# Nodino-RC7.net
KiCad netlist of a schematic drawn in EAGLE
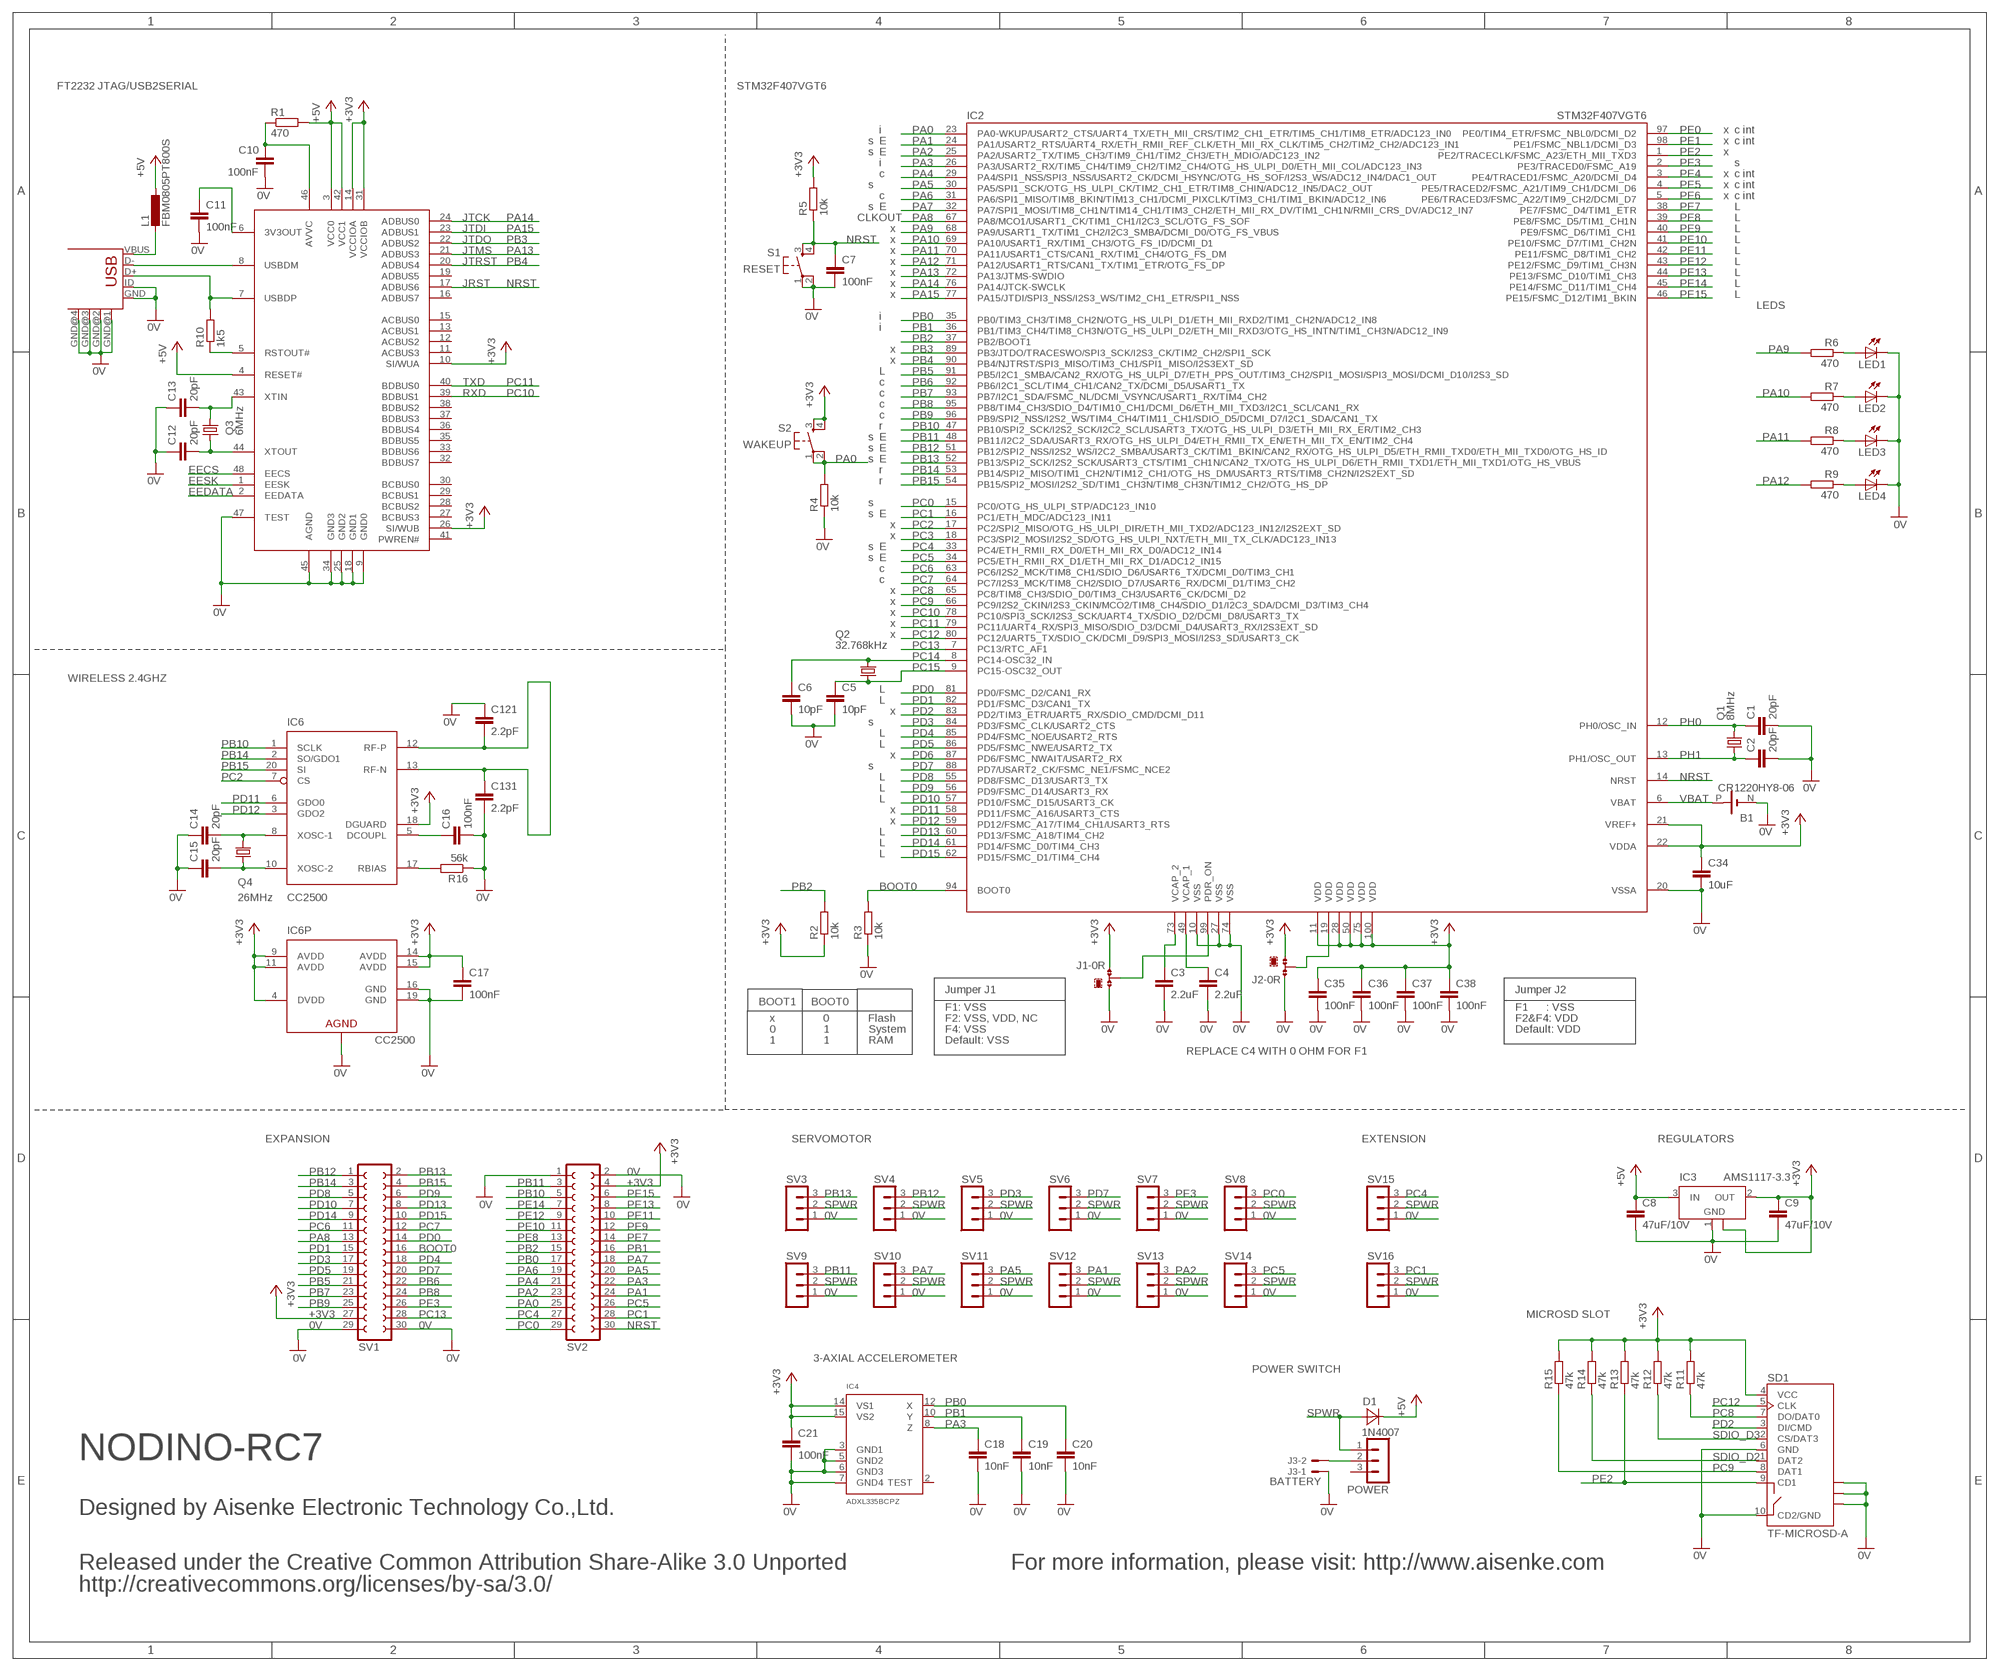
[diagram p0: schematic, sheet 1]

(export (version "E")
  (design (tool "Eeschema 10.0.6"))
  (components
    (comp (ref "B1")
      (value "CR1220HY8-06")
      (footprint "eagle-import:HY8-06")
      (libsource (lib "eagle-import") (part "CR1220HY8-06"))
    )
    (comp (ref "C1")
      (value "20pF")
      (footprint "eagle-import:C0603K")
      (libsource (lib "eagle-import") (part "C-EUC0603K"))
    )
    (comp (ref "C2")
      (value "20pF")
      (footprint "eagle-import:C0603K")
      (libsource (lib "eagle-import") (part "C-EUC0603K"))
    )
    (comp (ref "C3")
      (value "2.2uF")
      (footprint "eagle-import:C0603K")
      (libsource (lib "eagle-import") (part "C-EUC0603K"))
    )
    (comp (ref "C4")
      (value "2.2uF")
      (footprint "eagle-import:C0603K")
      (libsource (lib "eagle-import") (part "C-EUC0603K"))
    )
    (comp (ref "C5")
      (value "10pF")
      (footprint "eagle-import:C0603K")
      (libsource (lib "eagle-import") (part "C-EUC0603K"))
    )
    (comp (ref "C6")
      (value "10pF")
      (footprint "eagle-import:C0603K")
      (libsource (lib "eagle-import") (part "C-EUC0603K"))
    )
    (comp (ref "C7")
      (value "100nF")
      (footprint "eagle-import:C0603K")
      (libsource (lib "eagle-import") (part "C-EUC0603K"))
    )
    (comp (ref "C8")
      (value "47uF/10V")
      (footprint "eagle-import:C3225")
      (libsource (lib "eagle-import") (part "C-EUC3225"))
    )
    (comp (ref "C9")
      (value "47uF/10V")
      (footprint "eagle-import:C3225")
      (libsource (lib "eagle-import") (part "C-EUC3225"))
    )
    (comp (ref "C10")
      (value "100nF")
      (footprint "eagle-import:C0603K")
      (libsource (lib "eagle-import") (part "C-EUC0603K"))
    )
    (comp (ref "C11")
      (value "100nF")
      (footprint "eagle-import:C0603K")
      (libsource (lib "eagle-import") (part "C-EUC0603K"))
    )
    (comp (ref "C12")
      (value "20pF")
      (footprint "eagle-import:C0603K")
      (libsource (lib "eagle-import") (part "C-EUC0603K"))
    )
    (comp (ref "C13")
      (value "20pF")
      (footprint "eagle-import:C0603K")
      (libsource (lib "eagle-import") (part "C-EUC0603K"))
    )
    (comp (ref "C14")
      (value "20pF")
      (footprint "eagle-import:C0603K")
      (libsource (lib "eagle-import") (part "C-EUC0603K"))
    )
    (comp (ref "C15")
      (value "20pF")
      (footprint "eagle-import:C0603K")
      (libsource (lib "eagle-import") (part "C-EUC0603K"))
    )
    (comp (ref "C16")
      (value "100nF")
      (footprint "eagle-import:C0603K")
      (libsource (lib "eagle-import") (part "C-EUC0603K"))
    )
    (comp (ref "C17")
      (value "100nF")
      (footprint "eagle-import:C0603K")
      (libsource (lib "eagle-import") (part "C-EUC0603K"))
    )
    (comp (ref "C18")
      (value "10nF")
      (footprint "eagle-import:C0603K")
      (libsource (lib "eagle-import") (part "C-EUC0603K"))
    )
    (comp (ref "C19")
      (value "10nF")
      (footprint "eagle-import:C0603K")
      (libsource (lib "eagle-import") (part "C-EUC0603K"))
    )
    (comp (ref "C20")
      (value "10nF")
      (footprint "eagle-import:C0603K")
      (libsource (lib "eagle-import") (part "C-EUC0603K"))
    )
    (comp (ref "C21")
      (value "100nF")
      (footprint "eagle-import:C0603K")
      (libsource (lib "eagle-import") (part "C-EUC0603K"))
    )
    (comp (ref "C34")
      (value "10uF")
      (footprint "eagle-import:C0603K")
      (libsource (lib "eagle-import") (part "C-EUC0603K"))
    )
    (comp (ref "C35")
      (value "100nF")
      (footprint "eagle-import:C0603K")
      (libsource (lib "eagle-import") (part "C-EUC0603K"))
    )
    (comp (ref "C36")
      (value "100nF")
      (footprint "eagle-import:C0603K")
      (libsource (lib "eagle-import") (part "C-EUC0603K"))
    )
    (comp (ref "C37")
      (value "100nF")
      (footprint "eagle-import:C0603K")
      (libsource (lib "eagle-import") (part "C-EUC0603K"))
    )
    (comp (ref "C38")
      (value "100nF")
      (footprint "eagle-import:C0603K")
      (libsource (lib "eagle-import") (part "C-EUC0603K"))
    )
    (comp (ref "C121")
      (value "2.2pF")
      (footprint "eagle-import:C0603K")
      (libsource (lib "eagle-import") (part "C-EUC0603K"))
    )
    (comp (ref "C131")
      (value "2.2pF")
      (footprint "eagle-import:C0603K")
      (libsource (lib "eagle-import") (part "C-EUC0603K"))
    )
    (comp (ref "D1")
      (value "1N4007")
      (footprint "eagle-import:DO214AC")
      (libsource (lib "eagle-import") (part "1N4007"))
    )
    (comp (ref "IC1")
      (value "FT2232D")
      (footprint "eagle-import:LQFP48")
      (libsource (lib "eagle-import") (part "FT2232C"))
    )
    (comp (ref "IC2")
      (value "STM32F407VGT6")
      (footprint "eagle-import:LQFP100")
      (libsource (lib "eagle-import") (part "STM32F407VGT6"))
    )
    (comp (ref "IC3")
      (value "AMS1117-3.3")
      (footprint "eagle-import:SOT223")
      (libsource (lib "eagle-import") (part "AMS1117-3.3"))
    )
    (comp (ref "IC4")
      (value "ADXL335BCPZ")
      (footprint "eagle-import:LFCSP16-W")
      (libsource (lib "eagle-import") (part "ADXL335WAVE"))
    )
    (comp (ref "IC6")
      (value "CC2500")
      (footprint "eagle-import:QLP-20")
      (libsource (lib "eagle-import") (part "CC2500"))
    )
    (comp (ref "J1")
      (value "0R-JUMPA0603")
      (footprint "eagle-import:A0R-JMP0603K")
      (libsource (lib "eagle-import") (part "0R-JUMPA0603"))
    )
    (comp (ref "J2")
      (value "0R-JUMPA0603")
      (footprint "eagle-import:A0R-JMP0603K")
      (libsource (lib "eagle-import") (part "0R-JUMPA0603"))
    )
    (comp (ref "J3")
      (value "BATTERY")
      (footprint "eagle-import:6410-02")
      (libsource (lib "eagle-import") (part "22-?-0227-2021"))
    )
    (comp (ref "L1")
      (value "FBM0805PT800S")
      (footprint "eagle-import:L0805")
      (libsource (lib "eagle-import") (part "L-EUL0805"))
    )
    (comp (ref "LED1")
      (value "LEDCHIP-LED0805")
      (footprint "eagle-import:CHIP-LED0805")
      (libsource (lib "eagle-import") (part "LEDCHIP-LED0805"))
    )
    (comp (ref "LED2")
      (value "LEDCHIP-LED0805")
      (footprint "eagle-import:CHIP-LED0805")
      (libsource (lib "eagle-import") (part "LEDCHIP-LED0805"))
    )
    (comp (ref "LED3")
      (value "LEDCHIP-LED0805")
      (footprint "eagle-import:CHIP-LED0805")
      (libsource (lib "eagle-import") (part "LEDCHIP-LED0805"))
    )
    (comp (ref "LED4")
      (value "LEDCHIP-LED0805")
      (footprint "eagle-import:CHIP-LED0805")
      (libsource (lib "eagle-import") (part "LEDCHIP-LED0805"))
    )
    (comp (ref "POWER")
      (value "MA03-1")
      (footprint "eagle-import:MA03-1")
      (fields (field (name "OC_FARNELL") "unknown") (field (name "OC_NEWARK") "unknown"))
      (libsource (lib "eagle-import") (part "MA03-1"))
    )
    (comp (ref "Q1")
      (value "8MHz")
      (footprint "eagle-import:CSM-7X-DU")
      (libsource (lib "eagle-import") (part "CSM-7X-DU"))
    )
    (comp (ref "Q2")
      (value "32.768kHz")
      (footprint "eagle-import:MC-306")
      (fields (field (name "MPN") "MC-306 60.0KHZ  100PPM ,12.5PF"))
      (libsource (lib "eagle-import") (part "MC-306"))
    )
    (comp (ref "Q3")
      (value "6MHz")
      (footprint "eagle-import:CSM-7X-DU")
      (fields (field (name "OC_FARNELL") "unknown") (field (name "OC_NEWARK") "unknown"))
      (libsource (lib "eagle-import") (part "CSM-7X-DU"))
    )
    (comp (ref "Q4")
      (value "26MHz")
      (footprint "eagle-import:CSM-7X-DU")
      (fields (field (name "OC_FARNELL") "unknown") (field (name "OC_NEWARK") "unknown"))
      (libsource (lib "eagle-import") (part "CSM-7X-DU"))
    )
    (comp (ref "R1")
      (value "470")
      (footprint "eagle-import:R0603K")
      (libsource (lib "eagle-import") (part "R-EU_R0603K"))
    )
    (comp (ref "R2")
      (value "10k")
      (footprint "eagle-import:R0603K")
      (libsource (lib "eagle-import") (part "R-EU_R0603K"))
    )
    (comp (ref "R3")
      (value "10k")
      (footprint "eagle-import:R0603K")
      (libsource (lib "eagle-import") (part "R-EU_R0603K"))
    )
    (comp (ref "R4")
      (value "10k")
      (footprint "eagle-import:R0603K")
      (libsource (lib "eagle-import") (part "R-EU_R0603K"))
    )
    (comp (ref "R5")
      (value "10k")
      (footprint "eagle-import:R0603K")
      (libsource (lib "eagle-import") (part "R-EU_R0603K"))
    )
    (comp (ref "R6")
      (value "470")
      (footprint "eagle-import:R0603K")
      (libsource (lib "eagle-import") (part "R-EU_R0603K"))
    )
    (comp (ref "R7")
      (value "470")
      (footprint "eagle-import:R0603K")
      (libsource (lib "eagle-import") (part "R-EU_R0603K"))
    )
    (comp (ref "R8")
      (value "470")
      (footprint "eagle-import:R0603K")
      (libsource (lib "eagle-import") (part "R-EU_R0603K"))
    )
    (comp (ref "R9")
      (value "470")
      (footprint "eagle-import:R0603K")
      (libsource (lib "eagle-import") (part "R-EU_R0603K"))
    )
    (comp (ref "R10")
      (value "1k5")
      (footprint "eagle-import:R0603K")
      (libsource (lib "eagle-import") (part "R-EU_R0603K"))
    )
    (comp (ref "R11")
      (value "47k")
      (footprint "eagle-import:R0603K")
      (libsource (lib "eagle-import") (part "R-EU_R0603K"))
    )
    (comp (ref "R12")
      (value "47k")
      (footprint "eagle-import:R0603K")
      (libsource (lib "eagle-import") (part "R-EU_R0603K"))
    )
    (comp (ref "R13")
      (value "47k")
      (footprint "eagle-import:R0603K")
      (libsource (lib "eagle-import") (part "R-EU_R0603K"))
    )
    (comp (ref "R14")
      (value "47k")
      (footprint "eagle-import:R0603K")
      (libsource (lib "eagle-import") (part "R-EU_R0603K"))
    )
    (comp (ref "R15")
      (value "47k")
      (footprint "eagle-import:R0603K")
      (libsource (lib "eagle-import") (part "R-EU_R0603K"))
    )
    (comp (ref "R16")
      (value "56k")
      (footprint "eagle-import:R0603K")
      (libsource (lib "eagle-import") (part "R-EU_R0603K"))
    )
    (comp (ref "S1")
      (value "RESET")
      (footprint "eagle-import:ALCOSWITCH-SMD")
      (libsource (lib "eagle-import") (part "ALCOSWITCH-SMD"))
    )
    (comp (ref "S2")
      (value "WAKEUP")
      (footprint "eagle-import:ALCOSWITCH-SMD")
      (libsource (lib "eagle-import") (part "ALCOSWITCH-SMD"))
    )
    (comp (ref "SD1")
      (value "TF-MICROSD-A")
      (footprint "eagle-import:MICROSD_CD")
      (libsource (lib "eagle-import") (part "TF-MICROSD-A"))
    )
    (comp (ref "SV1")
      (value "FE15-2")
      (footprint "eagle-import:FE15-2")
      (libsource (lib "eagle-import") (part "FE15-2"))
    )
    (comp (ref "SV2")
      (value "FE15-2")
      (footprint "eagle-import:FE15-2")
      (libsource (lib "eagle-import") (part "FE15-2"))
    )
    (comp (ref "SV3")
      (value "MA03-1")
      (footprint "eagle-import:MA03-1")
      (libsource (lib "eagle-import") (part "MA03-1"))
    )
    (comp (ref "SV4")
      (value "MA03-1")
      (footprint "eagle-import:MA03-1")
      (libsource (lib "eagle-import") (part "MA03-1"))
    )
    (comp (ref "SV5")
      (value "MA03-1")
      (footprint "eagle-import:MA03-1")
      (libsource (lib "eagle-import") (part "MA03-1"))
    )
    (comp (ref "SV6")
      (value "MA03-1")
      (footprint "eagle-import:MA03-1")
      (libsource (lib "eagle-import") (part "MA03-1"))
    )
    (comp (ref "SV7")
      (value "MA03-1")
      (footprint "eagle-import:MA03-1")
      (libsource (lib "eagle-import") (part "MA03-1"))
    )
    (comp (ref "SV8")
      (value "MA03-1")
      (footprint "eagle-import:MA03-1")
      (libsource (lib "eagle-import") (part "MA03-1"))
    )
    (comp (ref "SV9")
      (value "MA03-1")
      (footprint "eagle-import:MA03-1")
      (libsource (lib "eagle-import") (part "MA03-1"))
    )
    (comp (ref "SV10")
      (value "MA03-1")
      (footprint "eagle-import:MA03-1")
      (libsource (lib "eagle-import") (part "MA03-1"))
    )
    (comp (ref "SV11")
      (value "MA03-1")
      (footprint "eagle-import:MA03-1")
      (libsource (lib "eagle-import") (part "MA03-1"))
    )
    (comp (ref "SV12")
      (value "MA03-1")
      (footprint "eagle-import:MA03-1")
      (libsource (lib "eagle-import") (part "MA03-1"))
    )
    (comp (ref "SV13")
      (value "MA03-1")
      (footprint "eagle-import:MA03-1")
      (libsource (lib "eagle-import") (part "MA03-1"))
    )
    (comp (ref "SV14")
      (value "MA03-1")
      (footprint "eagle-import:MA03-1")
      (libsource (lib "eagle-import") (part "MA03-1"))
    )
    (comp (ref "SV15")
      (value "MA03-1")
      (footprint "eagle-import:MA03-1")
      (libsource (lib "eagle-import") (part "MA03-1"))
    )
    (comp (ref "SV16")
      (value "MA03-1")
      (footprint "eagle-import:MA03-1")
      (libsource (lib "eagle-import") (part "MA03-1"))
    )
    (comp (ref "USB1")
      (value "USB-SHIELD")
      (footprint "eagle-import:USB-M-S1")
      (libsource (lib "eagle-import") (part "USB-SHIELD"))
    )
  )
  (nets
    (net (code "1") (name "+3V3") (class "Default")
      (node (ref "C17") (pin "1") (pinfunction "1_1") (pintype "passive"))
      (node (ref "C21") (pin "1") (pinfunction "1_1") (pintype "passive"))
      (node (ref "C34") (pin "1") (pinfunction "1_1") (pintype "passive"))
      (node (ref "C35") (pin "1") (pinfunction "1_1") (pintype "passive"))
      (node (ref "C36") (pin "1") (pinfunction "1_1") (pintype "passive"))
      (node (ref "C37") (pin "1") (pinfunction "1_1") (pintype "passive"))
      (node (ref "C38") (pin "1") (pinfunction "1_1") (pintype "passive"))
      (node (ref "C9") (pin "1") (pinfunction "1_1") (pintype "passive"))
      (node (ref "IC1") (pin "10") (pinfunction "SI/WUA_10") (pintype "bidirectional"))
      (node (ref "IC1") (pin "14") (pinfunction "VCCIOA_14") (pintype "bidirectional"))
      (node (ref "IC1") (pin "26") (pinfunction "SI/WUB_26") (pintype "bidirectional"))
      (node (ref "IC1") (pin "31") (pinfunction "VCCIOB_31") (pintype "bidirectional"))
      (node (ref "IC2") (pin "100") (pinfunction "VDD_100") (pintype "power_in"))
      (node (ref "IC2") (pin "11") (pinfunction "VDD_11") (pintype "power_in"))
      (node (ref "IC2") (pin "21") (pinfunction "VREF+_21") (pintype "input"))
      (node (ref "IC2") (pin "22") (pinfunction "VDDA_22") (pintype "power_in"))
      (node (ref "IC2") (pin "28") (pinfunction "VDD_28") (pintype "power_in"))
      (node (ref "IC2") (pin "50") (pinfunction "VDD_50") (pintype "power_in"))
      (node (ref "IC2") (pin "75") (pinfunction "VDD_75") (pintype "power_in"))
      (node (ref "IC3") (pin "2") (pinfunction "OUT_2") (pintype "output"))
      (node (ref "IC3") (pin "4") (pinfunction "GND_4") (pintype "power_in"))
      (node (ref "IC4") (pin "14") (pinfunction "VS1_14") (pintype "bidirectional"))
      (node (ref "IC4") (pin "15") (pinfunction "VS2_15") (pintype "bidirectional"))
      (node (ref "IC6") (pin "11") (pinfunction "AVDD_11") (pintype "power_in"))
      (node (ref "IC6") (pin "14") (pinfunction "AVDD_14") (pintype "power_in"))
      (node (ref "IC6") (pin "15") (pinfunction "AVDD_15") (pintype "power_in"))
      (node (ref "IC6") (pin "18") (pinfunction "DGUARD_18") (pintype "power_in"))
      (node (ref "IC6") (pin "4") (pinfunction "DVDD_4") (pintype "power_in"))
      (node (ref "IC6") (pin "9") (pinfunction "AVDD_9") (pintype "power_in"))
      (node (ref "J1") (pin "3") (pinfunction "3_3") (pintype "passive"))
      (node (ref "J2") (pin "1") (pinfunction "1_1") (pintype "passive"))
      (node (ref "R11") (pin "2") (pinfunction "2_2") (pintype "passive"))
      (node (ref "R12") (pin "2") (pinfunction "2_2") (pintype "passive"))
      (node (ref "R13") (pin "2") (pinfunction "2_2") (pintype "passive"))
      (node (ref "R14") (pin "2") (pinfunction "2_2") (pintype "passive"))
      (node (ref "R15") (pin "2") (pinfunction "2_2") (pintype "passive"))
      (node (ref "R2") (pin "1") (pinfunction "1_1") (pintype "passive"))
      (node (ref "R5") (pin "2") (pinfunction "2_2") (pintype "passive"))
      (node (ref "S2") (pin "3") (pinfunction "S_3") (pintype "passive"))
      (node (ref "S2") (pin "4") (pinfunction "S1_4") (pintype "passive"))
      (node (ref "SD1") (pin "4") (pinfunction "VCC_4") (pintype "power_in"))
      (node (ref "SV1") (pin "27") (pinfunction "27_27") (pintype "passive"))
      (node (ref "SV2") (pin "4") (pinfunction "4_4") (pintype "passive"))
    )
    (net (code "2") (name "+5V") (class "Default")
      (node (ref "C8") (pin "1") (pinfunction "1_1") (pintype "passive"))
      (node (ref "D1") (pin "C") (pinfunction "C_C") (pintype "passive"))
      (node (ref "IC1") (pin "3") (pinfunction "VCC0_3") (pintype "bidirectional"))
      (node (ref "IC1") (pin "4") (pinfunction "RESET#_4") (pintype "bidirectional"))
      (node (ref "IC1") (pin "42") (pinfunction "VCC1_42") (pintype "bidirectional"))
      (node (ref "IC3") (pin "3") (pinfunction "IN_3") (pintype "input"))
      (node (ref "L1") (pin "1") (pinfunction "1_1") (pintype "passive"))
      (node (ref "R1") (pin "2") (pinfunction "2_2") (pintype "passive"))
    )
    (net (code "3") (name "/BOOT0") (class "Default")
      (node (ref "IC2") (pin "94") (pinfunction "BOOT0_94") (pintype "input"))
      (node (ref "R3") (pin "2") (pinfunction "2_2") (pintype "passive"))
      (node (ref "SV1") (pin "16") (pinfunction "16_16") (pintype "passive"))
    )
    (net (code "4") (name "/EECS") (class "Default")
      (node (ref "IC1") (pin "48") (pinfunction "EECS_48") (pintype "bidirectional"))
    )
    (net (code "5") (name "/EEDATA") (class "Default")
      (node (ref "IC1") (pin "2") (pinfunction "EEDATA_2") (pintype "bidirectional"))
    )
    (net (code "6") (name "/EESK") (class "Default")
      (node (ref "IC1") (pin "1") (pinfunction "EESK_1") (pintype "bidirectional"))
    )
    (net (code "7") (name "/NRST") (class "Default")
      (node (ref "C7") (pin "1") (pinfunction "1_1") (pintype "passive"))
      (node (ref "IC1") (pin "17") (pinfunction "ADBUS6_17") (pintype "bidirectional"))
      (node (ref "IC2") (pin "14") (pinfunction "NRST_14") (pintype "input"))
      (node (ref "R5") (pin "1") (pinfunction "1_1") (pintype "passive"))
      (node (ref "S1") (pin "3") (pinfunction "S_3") (pintype "passive"))
      (node (ref "S1") (pin "4") (pinfunction "S1_4") (pintype "passive"))
      (node (ref "SV2") (pin "30") (pinfunction "30_30") (pintype "passive"))
    )
    (net (code "8") (name "/PA0") (class "Default")
      (node (ref "IC2") (pin "23") (pinfunction "PA0-WKUP/USART2_CTS/UART4_TX/ETH_MII_CRS/TIM2_CH1_ETR/TIM5_CH1/TIM8_ETR/ADC123_IN0_23") (pintype "bidirectional"))
      (node (ref "R4") (pin "2") (pinfunction "2_2") (pintype "passive"))
      (node (ref "S2") (pin "1") (pinfunction "P_1") (pintype "passive"))
      (node (ref "S2") (pin "2") (pinfunction "P1_2") (pintype "passive"))
      (node (ref "SV2") (pin "25") (pinfunction "25_25") (pintype "passive"))
    )
    (net (code "9") (name "/PA1") (class "Default")
      (node (ref "IC2") (pin "24") (pinfunction "PA1/USART2_RTS/UART4_RX/ETH_RMII_REF_CLK/ETH_MII_RX_CLK/TIM5_CH2/TIM2_CH2/ADC123_IN1_24") (pintype "bidirectional"))
      (node (ref "SV12") (pin "3") (pinfunction "3_3") (pintype "passive"))
      (node (ref "SV2") (pin "24") (pinfunction "24_24") (pintype "passive"))
    )
    (net (code "10") (name "/PA2") (class "Default")
      (node (ref "IC2") (pin "25") (pinfunction "PA2/USART2_TX/TIM5_CH3/TIM9_CH1/TIM2_CH3/ETH_MDIO/ADC123_IN2_25") (pintype "bidirectional"))
      (node (ref "SV13") (pin "3") (pinfunction "3_3") (pintype "passive"))
      (node (ref "SV2") (pin "23") (pinfunction "23_23") (pintype "passive"))
    )
    (net (code "11") (name "/PA3") (class "Default")
      (node (ref "C18") (pin "1") (pinfunction "1_1") (pintype "passive"))
      (node (ref "IC2") (pin "26") (pinfunction "PA3/USART2_RX/TIM5_CH4/TIM9_CH2/TIM2_CH4/OTG_HS_ULPI_D0/ETH_MII_COL/ADC123_IN3_26") (pintype "bidirectional"))
      (node (ref "IC4") (pin "8") (pinfunction "Z_8") (pintype "bidirectional"))
      (node (ref "SV2") (pin "22") (pinfunction "22_22") (pintype "passive"))
    )
    (net (code "12") (name "/PA4") (class "Default")
      (node (ref "IC2") (pin "29") (pinfunction "PA4/SPI1_NSS/SPI3_NSS/USART2_CK/DCMI_HSYNC/OTG_HS_SOF/I2S3_WS/ADC12_IN4/DAC1_OUT_29") (pintype "bidirectional"))
      (node (ref "SV2") (pin "21") (pinfunction "21_21") (pintype "passive"))
    )
    (net (code "13") (name "/PA5") (class "Default")
      (node (ref "IC2") (pin "30") (pinfunction "PA5/SPI1_SCK/OTG_HS_ULPI_CK/TIM2_CH1_ETR/TIM8_CHIN/ADC12_IN5/DAC2_OUT_30") (pintype "bidirectional"))
      (node (ref "SV11") (pin "3") (pinfunction "3_3") (pintype "passive"))
      (node (ref "SV2") (pin "20") (pinfunction "20_20") (pintype "passive"))
    )
    (net (code "14") (name "/PA6") (class "Default")
      (node (ref "IC2") (pin "31") (pinfunction "PA6/SPI1_MISO/TIM8_BKIN/TIM13_CH1/DCMI_PIXCLK/TIM3_CH1/TIM1_BKIN/ADC12_IN6_31") (pintype "bidirectional"))
      (node (ref "SV2") (pin "19") (pinfunction "19_19") (pintype "passive"))
    )
    (net (code "15") (name "/PA7") (class "Default")
      (node (ref "IC2") (pin "32") (pinfunction "PA7/SPI1_MOSI/TIM8_CH1N/TIM14_CH1/TIM3_CH2/ETH_MII_RX_DV/TIM1_CH1N/RMII_CRS_DV/ADC12_IN7_32") (pintype "bidirectional"))
      (node (ref "SV10") (pin "3") (pinfunction "3_3") (pintype "passive"))
      (node (ref "SV2") (pin "18") (pinfunction "18_18") (pintype "passive"))
    )
    (net (code "16") (name "/PA8") (class "Default")
      (node (ref "IC2") (pin "67") (pinfunction "PA8/MCO1/USART1_CK/TIM1_CH1/I2C3_SCL/OTG_FS_SOF_67") (pintype "bidirectional"))
      (node (ref "SV1") (pin "13") (pinfunction "13_13") (pintype "passive"))
    )
    (net (code "17") (name "/PA9") (class "Default")
      (node (ref "IC2") (pin "68") (pinfunction "PA9/USART1_TX/TIM1_CH2/I2C3_SMBA/DCMI_D0/OTG_FS_VBUS_68") (pintype "bidirectional"))
      (node (ref "R6") (pin "2") (pinfunction "2_2") (pintype "passive"))
    )
    (net (code "18") (name "/PA10") (class "Default")
      (node (ref "IC2") (pin "69") (pinfunction "PA10/USART1_RX/TIM1_CH3/OTG_FS_ID/DCMI_D1_69") (pintype "bidirectional"))
      (node (ref "R7") (pin "2") (pinfunction "2_2") (pintype "passive"))
    )
    (net (code "19") (name "/PA11") (class "Default")
      (node (ref "IC2") (pin "70") (pinfunction "PA11/USART1_CTS/CAN1_RX/TIM1_CH4/OTG_FS_DM_70") (pintype "bidirectional"))
      (node (ref "R8") (pin "2") (pinfunction "2_2") (pintype "passive"))
    )
    (net (code "20") (name "/PA12") (class "Default")
      (node (ref "IC2") (pin "71") (pinfunction "PA12/USART1_RTS/CAN1_TX/TIM1_ETR/OTG_FS_DP_71") (pintype "bidirectional"))
      (node (ref "R9") (pin "2") (pinfunction "2_2") (pintype "passive"))
    )
    (net (code "21") (name "/PA13") (class "Default")
      (node (ref "IC1") (pin "21") (pinfunction "ADBUS3_21") (pintype "bidirectional"))
      (node (ref "IC2") (pin "72") (pinfunction "PA13/JTMS-SWDIO_72") (pintype "bidirectional"))
    )
    (net (code "22") (name "/PA14") (class "Default")
      (node (ref "IC1") (pin "24") (pinfunction "ADBUS0_24") (pintype "bidirectional"))
      (node (ref "IC2") (pin "76") (pinfunction "PA14/JTCK-SWCLK_76") (pintype "bidirectional"))
    )
    (net (code "23") (name "/PA15") (class "Default")
      (node (ref "IC1") (pin "23") (pinfunction "ADBUS1_23") (pintype "bidirectional"))
      (node (ref "IC2") (pin "77") (pinfunction "PA15/JTDI/SPI3_NSS/I2S3_WS/TIM2_CH1_ETR/SPI1_NSS_77") (pintype "bidirectional"))
    )
    (net (code "24") (name "/PB0") (class "Default")
      (node (ref "C20") (pin "1") (pinfunction "1_1") (pintype "passive"))
      (node (ref "IC2") (pin "35") (pinfunction "PB0/TIM3_CH3/TIM8_CH2N/OTG_HS_ULPI_D1/ETH_MII_RXD2/TIM1_CH2N/ADC12_IN8_35") (pintype "bidirectional"))
      (node (ref "IC4") (pin "12") (pinfunction "X_12") (pintype "bidirectional"))
      (node (ref "SV2") (pin "17") (pinfunction "17_17") (pintype "passive"))
    )
    (net (code "25") (name "/PB1") (class "Default")
      (node (ref "C19") (pin "1") (pinfunction "1_1") (pintype "passive"))
      (node (ref "IC2") (pin "36") (pinfunction "PB1/TIM3_CH4/TIM8_CH3N/OTG_HS_ULPI_D2/ETH_MII_RXD3/OTG_HS_INTN/TIM1_CH3N/ADC12_IN9_36") (pintype "bidirectional"))
      (node (ref "IC4") (pin "10") (pinfunction "Y_10") (pintype "bidirectional"))
      (node (ref "SV2") (pin "16") (pinfunction "16_16") (pintype "passive"))
    )
    (net (code "26") (name "/PB2") (class "Default")
      (node (ref "IC2") (pin "37") (pinfunction "PB2/BOOT1_37") (pintype "bidirectional"))
      (node (ref "R2") (pin "2") (pinfunction "2_2") (pintype "passive"))
      (node (ref "SV2") (pin "15") (pinfunction "15_15") (pintype "passive"))
    )
    (net (code "27") (name "/PB3") (class "Default")
      (node (ref "IC1") (pin "22") (pinfunction "ADBUS2_22") (pintype "bidirectional"))
      (node (ref "IC2") (pin "89") (pinfunction "PB3/JTDO/TRACESWO/SPI3_SCK/I2S3_CK/TIM2_CH2/SPI1_SCK_89") (pintype "bidirectional"))
    )
    (net (code "28") (name "/PB4") (class "Default")
      (node (ref "IC1") (pin "20") (pinfunction "ADBUS4_20") (pintype "bidirectional"))
      (node (ref "IC2") (pin "90") (pinfunction "PB4/NJTRST/SPI3_MISO/TIM3_CH1/SPI1_MISO/I2S3EXT_SD_90") (pintype "bidirectional"))
    )
    (net (code "29") (name "/PB5") (class "Default")
      (node (ref "IC2") (pin "91") (pinfunction "PB5/I2C1_SMBA/CAN2_RX/OTG_HS_ULPI_D7/ETH_PPS_OUT/TIM3_CH2/SPI1_MOSI/SPI3_MOSI/DCMI_D10/I2S3_SD_91") (pintype "bidirectional"))
      (node (ref "SV1") (pin "21") (pinfunction "21_21") (pintype "passive"))
    )
    (net (code "30") (name "/PB6") (class "Default")
      (node (ref "IC2") (pin "92") (pinfunction "PB6/I2C1_SCL/TIM4_CH1/CAN2_TX/DCMI_D5/USART1_TX_92") (pintype "bidirectional"))
      (node (ref "SV1") (pin "22") (pinfunction "22_22") (pintype "passive"))
    )
    (net (code "31") (name "/PB7") (class "Default")
      (node (ref "IC2") (pin "93") (pinfunction "PB7/I2C1_SDA/FSMC_NL/DCMI_VSYNC/USART1_RX/TIM4_CH2_93") (pintype "bidirectional"))
      (node (ref "SV1") (pin "23") (pinfunction "23_23") (pintype "passive"))
    )
    (net (code "32") (name "/PB8") (class "Default")
      (node (ref "IC2") (pin "95") (pinfunction "PB8/TIM4_CH3/SDIO_D4/TIM10_CH1/DCMI_D6/ETH_MII_TXD3/I2C1_SCL/CAN1_RX_95") (pintype "bidirectional"))
      (node (ref "SV1") (pin "24") (pinfunction "24_24") (pintype "passive"))
    )
    (net (code "33") (name "/PB9") (class "Default")
      (node (ref "IC2") (pin "96") (pinfunction "PB9/SPI2_NSS/I2S2_WS/TIM4_CH4/TIM11_CH1/SDIO_D5/DCMI_D7/I2C1_SDA/CAN1_TX_96") (pintype "bidirectional"))
      (node (ref "SV1") (pin "25") (pinfunction "25_25") (pintype "passive"))
    )
    (net (code "34") (name "/PB10") (class "Default")
      (node (ref "IC2") (pin "47") (pinfunction "PB10/SPI2_SCK/I2S2_SCK/I2C2_SCL/USART3_TX/OTG_HS_ULPI_D3/ETH_MII_RX_ER/TIM2_CH3_47") (pintype "bidirectional"))
      (node (ref "IC6") (pin "1") (pinfunction "SCLK_1") (pintype "input"))
      (node (ref "SV2") (pin "5") (pinfunction "5_5") (pintype "passive"))
    )
    (net (code "35") (name "/PB11") (class "Default")
      (node (ref "IC2") (pin "48") (pinfunction "PB11/I2C2_SDA/USART3_RX/OTG_HS_ULPI_D4/ETH_RMII_TX_EN/ETH_MII_TX_EN/TIM2_CH4_48") (pintype "bidirectional"))
      (node (ref "SV2") (pin "3") (pinfunction "3_3") (pintype "passive"))
      (node (ref "SV9") (pin "3") (pinfunction "3_3") (pintype "passive"))
    )
    (net (code "36") (name "/PB12") (class "Default")
      (node (ref "IC2") (pin "51") (pinfunction "PB12/SPI2_NSS/I2S2_WS/I2C2_SMBA/USART3_CK/TIM1_BKIN/CAN2_RX/OTG_HS_ULPI_D5/ETH_RMII_TXD0/ETH_MII_TXD0/OTG_HS_ID_51") (pintype "bidirectional"))
      (node (ref "SV1") (pin "1") (pinfunction "1_1") (pintype "passive"))
      (node (ref "SV4") (pin "3") (pinfunction "3_3") (pintype "passive"))
    )
    (net (code "37") (name "/PB13") (class "Default")
      (node (ref "IC2") (pin "52") (pinfunction "PB13/SPI2_SCK/I2S2_SCK/USART3_CTS/TIM1_CH1N/CAN2_TX/OTG_HS_ULPI_D6/ETH_RMII_TXD1/ETH_MII_TXD1/OTG_HS_VBUS_52") (pintype "bidirectional"))
      (node (ref "SV1") (pin "2") (pinfunction "2_2") (pintype "passive"))
      (node (ref "SV3") (pin "3") (pinfunction "3_3") (pintype "passive"))
    )
    (net (code "38") (name "/PB14") (class "Default")
      (node (ref "IC2") (pin "53") (pinfunction "PB14/SPI2_MISO/TIM1_CH2N/TIM12_CH1/OTG_HS_DM/USART3_RTS/TIM8_CH2N/I2S2EXT_SD_53") (pintype "bidirectional"))
      (node (ref "IC6") (pin "2") (pinfunction "SO/GDO1_2") (pintype "output"))
      (node (ref "SV1") (pin "3") (pinfunction "3_3") (pintype "passive"))
    )
    (net (code "39") (name "/PB15") (class "Default")
      (node (ref "IC2") (pin "54") (pinfunction "PB15/SPI2_MOSI/I2S2_SD/TIM1_CH3N/TIM8_CH3N/TIM12_CH2/OTG_HS_DP_54") (pintype "bidirectional"))
      (node (ref "IC6") (pin "20") (pinfunction "SI_20") (pintype "input"))
      (node (ref "SV1") (pin "4") (pinfunction "4_4") (pintype "passive"))
    )
    (net (code "40") (name "/PC0") (class "Default")
      (node (ref "IC2") (pin "15") (pinfunction "PC0/OTG_HS_ULPI_STP/ADC123_IN10_15") (pintype "bidirectional"))
      (node (ref "SV2") (pin "29") (pinfunction "29_29") (pintype "passive"))
      (node (ref "SV8") (pin "3") (pinfunction "3_3") (pintype "passive"))
    )
    (net (code "41") (name "/PC1") (class "Default")
      (node (ref "IC2") (pin "16") (pinfunction "PC1/ETH_MDC/ADC123_IN11_16") (pintype "bidirectional"))
      (node (ref "SV16") (pin "3") (pinfunction "3_3") (pintype "passive"))
      (node (ref "SV2") (pin "28") (pinfunction "28_28") (pintype "passive"))
    )
    (net (code "42") (name "/PC2") (class "Default")
      (node (ref "IC2") (pin "17") (pinfunction "PC2/SPI2_MISO/OTG_HS_ULPI_DIR/ETH_MII_TXD2/ADC123_IN12/I2S2EXT_SD_17") (pintype "bidirectional"))
      (node (ref "IC6") (pin "7") (pinfunction "CS_7") (pintype "input"))
    )
    (net (code "43") (name "/PC3") (class "Default")
      (node (ref "IC2") (pin "18") (pinfunction "PC3/SPI2_MOSI/I2S2_SD/OTG_HS_ULPI_NXT/ETH_MII_TX_CLK/ADC123_IN13_18") (pintype "bidirectional"))
    )
    (net (code "44") (name "/PC4") (class "Default")
      (node (ref "IC2") (pin "33") (pinfunction "PC4/ETH_RMII_RX_D0/ETH_MII_RX_D0/ADC12_IN14_33") (pintype "bidirectional"))
      (node (ref "SV15") (pin "3") (pinfunction "3_3") (pintype "passive"))
      (node (ref "SV2") (pin "27") (pinfunction "27_27") (pintype "passive"))
    )
    (net (code "45") (name "/PC5") (class "Default")
      (node (ref "IC2") (pin "34") (pinfunction "PC5/ETH_RMII_RX_D1/ETH_MII_RX_D1/ADC12_IN15_34") (pintype "bidirectional"))
      (node (ref "SV14") (pin "3") (pinfunction "3_3") (pintype "passive"))
      (node (ref "SV2") (pin "26") (pinfunction "26_26") (pintype "passive"))
    )
    (net (code "46") (name "/PC6") (class "Default")
      (node (ref "IC2") (pin "63") (pinfunction "PC6/I2S2_MCK/TIM8_CH1/SDIO_D6/USART6_TX/DCMI_D0/TIM3_CH1_63") (pintype "bidirectional"))
      (node (ref "SV1") (pin "11") (pinfunction "11_11") (pintype "passive"))
    )
    (net (code "47") (name "/PC7") (class "Default")
      (node (ref "IC2") (pin "64") (pinfunction "PC7/I2S3_MCK/TIM8_CH2/SDIO_D7/USART6_RX/DCMI_D1/TIM3_CH2_64") (pintype "bidirectional"))
      (node (ref "SV1") (pin "12") (pinfunction "12_12") (pintype "passive"))
    )
    (net (code "48") (name "/PC8") (class "Default")
      (node (ref "IC2") (pin "65") (pinfunction "PC8/TIM8_CH3/SDIO_D0/TIM3_CH3/USART6_CK/DCMI_D2_65") (pintype "bidirectional"))
      (node (ref "R11") (pin "1") (pinfunction "1_1") (pintype "passive"))
      (node (ref "SD1") (pin "7") (pinfunction "DO/DAT0_7") (pintype "bidirectional"))
    )
    (net (code "49") (name "/PC9") (class "Default")
      (node (ref "IC2") (pin "66") (pinfunction "PC9/I2S2_CKIN/I2S3_CKIN/MCO2/TIM8_CH4/SDIO_D1/I2C3_SDA/DCMI_D3/TIM3_CH4_66") (pintype "bidirectional"))
      (node (ref "R15") (pin "1") (pinfunction "1_1") (pintype "passive"))
      (node (ref "SD1") (pin "8") (pinfunction "DAT1_8") (pintype "bidirectional"))
    )
    (net (code "50") (name "/PC10") (class "Default")
      (node (ref "IC1") (pin "39") (pinfunction "BDBUS1_39") (pintype "bidirectional"))
      (node (ref "IC2") (pin "78") (pinfunction "PC10/SPI3_SCK/I2S3_SCK/UART4_TX/SDIO_D2/DCMI_D8/USART3_TX_78") (pintype "bidirectional"))
    )
    (net (code "51") (name "/PC11") (class "Default")
      (node (ref "IC1") (pin "40") (pinfunction "BDBUS0_40") (pintype "bidirectional"))
      (node (ref "IC2") (pin "79") (pinfunction "PC11/UART4_RX/SPI3_MISO/SDIO_D3/DCMI_D4/USART3_RX/I2S3EXT_SD_79") (pintype "bidirectional"))
    )
    (net (code "52") (name "/PC12") (class "Default")
      (node (ref "IC2") (pin "80") (pinfunction "PC12/UART5_TX/SDIO_CK/DCMI_D9/SPI3_MOSI/I2S3_SD/USART3_CK_80") (pintype "bidirectional"))
      (node (ref "SD1") (pin "5") (pinfunction "CLK_5") (pintype "input"))
    )
    (net (code "53") (name "/PC13") (class "Default")
      (node (ref "IC2") (pin "7") (pinfunction "PC13/RTC_AF1_7") (pintype "bidirectional"))
      (node (ref "SV1") (pin "28") (pinfunction "28_28") (pintype "passive"))
    )
    (net (code "54") (name "/PC14") (class "Default")
      (node (ref "C6") (pin "1") (pinfunction "1_1") (pintype "passive"))
      (node (ref "IC2") (pin "8") (pinfunction "PC14-OSC32_IN_8") (pintype "bidirectional"))
      (node (ref "Q2") (pin "4") (pinfunction "2_4") (pintype "passive"))
    )
    (net (code "55") (name "/PC15") (class "Default")
      (node (ref "C5") (pin "1") (pinfunction "1_1") (pintype "passive"))
      (node (ref "IC2") (pin "9") (pinfunction "PC15-OSC32_OUT_9") (pintype "bidirectional"))
      (node (ref "Q2") (pin "1") (pinfunction "1_1") (pintype "passive"))
    )
    (net (code "56") (name "/PD0") (class "Default")
      (node (ref "IC2") (pin "81") (pinfunction "PD0/FSMC_D2/CAN1_RX_81") (pintype "bidirectional"))
      (node (ref "SV1") (pin "14") (pinfunction "14_14") (pintype "passive"))
    )
    (net (code "57") (name "/PD1") (class "Default")
      (node (ref "IC2") (pin "82") (pinfunction "PD1/FSMC_D3/CAN1_TX_82") (pintype "bidirectional"))
      (node (ref "SV1") (pin "15") (pinfunction "15_15") (pintype "passive"))
    )
    (net (code "58") (name "/PD2") (class "Default")
      (node (ref "IC2") (pin "83") (pinfunction "PD2/TIM3_ETR/UART5_RX/SDIO_CMD/DCMI_D11_83") (pintype "bidirectional"))
      (node (ref "SD1") (pin "3") (pinfunction "DI/CMD_3") (pintype "bidirectional"))
    )
    (net (code "59") (name "/PD3") (class "Default")
      (node (ref "IC2") (pin "84") (pinfunction "PD3/FSMC_CLK/USART2_CTS_84") (pintype "bidirectional"))
      (node (ref "SV1") (pin "17") (pinfunction "17_17") (pintype "passive"))
      (node (ref "SV5") (pin "3") (pinfunction "3_3") (pintype "passive"))
    )
    (net (code "60") (name "/PD4") (class "Default")
      (node (ref "IC2") (pin "85") (pinfunction "PD4/FSMC_NOE/USART2_RTS_85") (pintype "bidirectional"))
      (node (ref "SV1") (pin "18") (pinfunction "18_18") (pintype "passive"))
    )
    (net (code "61") (name "/PD5") (class "Default")
      (node (ref "IC2") (pin "86") (pinfunction "PD5/FSMC_NWE/USART2_TX_86") (pintype "bidirectional"))
      (node (ref "SV1") (pin "19") (pinfunction "19_19") (pintype "passive"))
    )
    (net (code "62") (name "/PD6") (class "Default")
      (node (ref "IC2") (pin "87") (pinfunction "PD6/FSMC_NWAIT/USART2_RX_87") (pintype "bidirectional"))
    )
    (net (code "63") (name "/PD7") (class "Default")
      (node (ref "IC2") (pin "88") (pinfunction "PD7/USART2_CK/FSMC_NE1/FSMC_NCE2_88") (pintype "bidirectional"))
      (node (ref "SV1") (pin "20") (pinfunction "20_20") (pintype "passive"))
      (node (ref "SV6") (pin "3") (pinfunction "3_3") (pintype "passive"))
    )
    (net (code "64") (name "/PD8") (class "Default")
      (node (ref "IC2") (pin "55") (pinfunction "PD8/FSMC_D13/USART3_TX_55") (pintype "bidirectional"))
      (node (ref "SV1") (pin "5") (pinfunction "5_5") (pintype "passive"))
    )
    (net (code "65") (name "/PD9") (class "Default")
      (node (ref "IC2") (pin "56") (pinfunction "PD9/FSMC_D14/USART3_RX_56") (pintype "bidirectional"))
      (node (ref "SV1") (pin "6") (pinfunction "6_6") (pintype "passive"))
    )
    (net (code "66") (name "/PD10") (class "Default")
      (node (ref "IC2") (pin "57") (pinfunction "PD10/FSMC_D15/USART3_CK_57") (pintype "bidirectional"))
      (node (ref "SV1") (pin "7") (pinfunction "7_7") (pintype "passive"))
    )
    (net (code "67") (name "/PD11") (class "Default")
      (node (ref "IC2") (pin "58") (pinfunction "PD11/FSMC_A16/USART3_CTS_58") (pintype "bidirectional"))
      (node (ref "IC6") (pin "6") (pinfunction "GDO0_6") (pintype "output"))
    )
    (net (code "68") (name "/PD12") (class "Default")
      (node (ref "IC2") (pin "59") (pinfunction "PD12/FSMC_A17/TIM4_CH1/USART3_RTS_59") (pintype "bidirectional"))
      (node (ref "IC6") (pin "3") (pinfunction "GDO2_3") (pintype "output"))
    )
    (net (code "69") (name "/PD13") (class "Default")
      (node (ref "IC2") (pin "60") (pinfunction "PD13/FSMC_A18/TIM4_CH2_60") (pintype "bidirectional"))
      (node (ref "SV1") (pin "8") (pinfunction "8_8") (pintype "passive"))
    )
    (net (code "70") (name "/PD14") (class "Default")
      (node (ref "IC2") (pin "61") (pinfunction "PD14/FSMC_D0/TIM4_CH3_61") (pintype "bidirectional"))
      (node (ref "SV1") (pin "9") (pinfunction "9_9") (pintype "passive"))
    )
    (net (code "71") (name "/PD15") (class "Default")
      (node (ref "IC2") (pin "62") (pinfunction "PD15/FSMC_D1/TIM4_CH4_62") (pintype "bidirectional"))
      (node (ref "SV1") (pin "10") (pinfunction "10_10") (pintype "passive"))
    )
    (net (code "72") (name "/PE0") (class "Default")
      (node (ref "IC2") (pin "97") (pinfunction "PE0/TIM4_ETR/FSMC_NBL0/DCMI_D2_97") (pintype "bidirectional"))
    )
    (net (code "73") (name "/PE1") (class "Default")
      (node (ref "IC2") (pin "98") (pinfunction "PE1/FSMC_NBL1/DCMI_D3_98") (pintype "bidirectional"))
    )
    (net (code "74") (name "/PE2") (class "Default")
      (node (ref "IC2") (pin "1") (pinfunction "PE2/TRACECLK/FSMC_A23/ETH_MII_TXD3_1") (pintype "bidirectional"))
      (node (ref "R13") (pin "1") (pinfunction "1_1") (pintype "passive"))
      (node (ref "SD1") (pin "9") (pinfunction "CD1_9") (pintype "bidirectional"))
    )
    (net (code "75") (name "/PE3") (class "Default")
      (node (ref "IC2") (pin "2") (pinfunction "PE3/TRACED0/FSMC_A19_2") (pintype "bidirectional"))
      (node (ref "SV1") (pin "26") (pinfunction "26_26") (pintype "passive"))
      (node (ref "SV7") (pin "3") (pinfunction "3_3") (pintype "passive"))
    )
    (net (code "76") (name "/PE4") (class "Default")
      (node (ref "IC2") (pin "3") (pinfunction "PE4/TRACED1/FSMC_A20/DCMI_D4_3") (pintype "bidirectional"))
    )
    (net (code "77") (name "/PE5") (class "Default")
      (node (ref "IC2") (pin "4") (pinfunction "PE5/TRACED2/FSMC_A21/TIM9_CH1/DCMI_D6_4") (pintype "bidirectional"))
    )
    (net (code "78") (name "/PE6") (class "Default")
      (node (ref "IC2") (pin "5") (pinfunction "PE6/TRACED3/FSMC_A22/TIM9_CH2/DCMI_D7_5") (pintype "bidirectional"))
    )
    (net (code "79") (name "/PE7") (class "Default")
      (node (ref "IC2") (pin "38") (pinfunction "PE7/FSMC_D4/TIM1_ETR_38") (pintype "bidirectional"))
      (node (ref "SV2") (pin "14") (pinfunction "14_14") (pintype "passive"))
    )
    (net (code "80") (name "/PE8") (class "Default")
      (node (ref "IC2") (pin "39") (pinfunction "PE8/FSMC_D5/TIM1_CH1N_39") (pintype "bidirectional"))
      (node (ref "SV2") (pin "13") (pinfunction "13_13") (pintype "passive"))
    )
    (net (code "81") (name "/PE9") (class "Default")
      (node (ref "IC2") (pin "40") (pinfunction "PE9/FSMC_D6/TIM1_CH1_40") (pintype "bidirectional"))
      (node (ref "SV2") (pin "12") (pinfunction "12_12") (pintype "passive"))
    )
    (net (code "82") (name "/PE10") (class "Default")
      (node (ref "IC2") (pin "41") (pinfunction "PE10/FSMC_D7/TIM1_CH2N_41") (pintype "bidirectional"))
      (node (ref "SV2") (pin "11") (pinfunction "11_11") (pintype "passive"))
    )
    (net (code "83") (name "/PE11") (class "Default")
      (node (ref "IC2") (pin "42") (pinfunction "PE11/FSMC_D8/TIM1_CH2_42") (pintype "bidirectional"))
      (node (ref "SV2") (pin "10") (pinfunction "10_10") (pintype "passive"))
    )
    (net (code "84") (name "/PE12") (class "Default")
      (node (ref "IC2") (pin "43") (pinfunction "PE12/FSMC_D9/TIM1_CH3N_43") (pintype "bidirectional"))
      (node (ref "SV2") (pin "9") (pinfunction "9_9") (pintype "passive"))
    )
    (net (code "85") (name "/PE13") (class "Default")
      (node (ref "IC2") (pin "44") (pinfunction "PE13/FSMC_D10/TIM1_CH3_44") (pintype "bidirectional"))
      (node (ref "SV2") (pin "8") (pinfunction "8_8") (pintype "passive"))
    )
    (net (code "86") (name "/PE14") (class "Default")
      (node (ref "IC2") (pin "45") (pinfunction "PE14/FSMC_D11/TIM1_CH4_45") (pintype "bidirectional"))
      (node (ref "SV2") (pin "7") (pinfunction "7_7") (pintype "passive"))
    )
    (net (code "87") (name "/PE15") (class "Default")
      (node (ref "IC2") (pin "46") (pinfunction "PE15/FSMC_D12/TIM1_BKIN_46") (pintype "bidirectional"))
      (node (ref "SV2") (pin "6") (pinfunction "6_6") (pintype "passive"))
    )
    (net (code "88") (name "/PH0") (class "Default")
      (node (ref "C1") (pin "1") (pinfunction "1_1") (pintype "passive"))
      (node (ref "IC2") (pin "12") (pinfunction "PH0/OSC_IN_12") (pintype "input"))
      (node (ref "Q1") (pin "2") (pinfunction "2_2") (pintype "passive"))
    )
    (net (code "89") (name "/PH1") (class "Default")
      (node (ref "C2") (pin "1") (pinfunction "1_1") (pintype "passive"))
      (node (ref "IC2") (pin "13") (pinfunction "PH1/OSC_OUT_13") (pintype "output"))
      (node (ref "Q1") (pin "1") (pinfunction "1_1") (pintype "passive"))
    )
    (net (code "90") (name "/SDIO_D2") (class "Default")
      (node (ref "R14") (pin "1") (pinfunction "1_1") (pintype "passive"))
      (node (ref "SD1") (pin "1") (pinfunction "DAT2_1") (pintype "bidirectional"))
    )
    (net (code "91") (name "/SDIO_D3") (class "Default")
      (node (ref "R12") (pin "1") (pinfunction "1_1") (pintype "passive"))
      (node (ref "SD1") (pin "2") (pinfunction "CS/DAT3_2") (pintype "bidirectional"))
    )
    (net (code "92") (name "/SPWR") (class "Default")
      (node (ref "D1") (pin "A") (pinfunction "A_A") (pintype "passive"))
      (node (ref "POWER") (pin "1") (pinfunction "1_1") (pintype "passive"))
      (node (ref "SV10") (pin "2") (pinfunction "2_2") (pintype "passive"))
      (node (ref "SV11") (pin "2") (pinfunction "2_2") (pintype "passive"))
      (node (ref "SV12") (pin "2") (pinfunction "2_2") (pintype "passive"))
      (node (ref "SV13") (pin "2") (pinfunction "2_2") (pintype "passive"))
      (node (ref "SV14") (pin "2") (pinfunction "2_2") (pintype "passive"))
      (node (ref "SV15") (pin "2") (pinfunction "2_2") (pintype "passive"))
      (node (ref "SV16") (pin "2") (pinfunction "2_2") (pintype "passive"))
      (node (ref "SV3") (pin "2") (pinfunction "2_2") (pintype "passive"))
      (node (ref "SV4") (pin "2") (pinfunction "2_2") (pintype "passive"))
      (node (ref "SV5") (pin "2") (pinfunction "2_2") (pintype "passive"))
      (node (ref "SV6") (pin "2") (pinfunction "2_2") (pintype "passive"))
      (node (ref "SV7") (pin "2") (pinfunction "2_2") (pintype "passive"))
      (node (ref "SV8") (pin "2") (pinfunction "2_2") (pintype "passive"))
      (node (ref "SV9") (pin "2") (pinfunction "2_2") (pintype "passive"))
    )
    (net (code "93") (name "/VBAT") (class "Default")
      (node (ref "B1") (pin "P") (pinfunction "+_P") (pintype "passive"))
      (node (ref "IC2") (pin "6") (pinfunction "VBAT_6") (pintype "input"))
    )
    (net (code "94") (name "0V") (class "Default")
      (node (ref "B1") (pin "N") (pinfunction "-_N") (pintype "passive"))
      (node (ref "C1") (pin "2") (pinfunction "2_2") (pintype "passive"))
      (node (ref "C10") (pin "2") (pinfunction "2_2") (pintype "passive"))
      (node (ref "C11") (pin "2") (pinfunction "2_2") (pintype "passive"))
      (node (ref "C12") (pin "1") (pinfunction "1_1") (pintype "passive"))
      (node (ref "C121") (pin "1") (pinfunction "1_1") (pintype "passive"))
      (node (ref "C13") (pin "1") (pinfunction "1_1") (pintype "passive"))
      (node (ref "C131") (pin "2") (pinfunction "2_2") (pintype "passive"))
      (node (ref "C14") (pin "1") (pinfunction "1_1") (pintype "passive"))
      (node (ref "C15") (pin "1") (pinfunction "1_1") (pintype "passive"))
      (node (ref "C16") (pin "2") (pinfunction "2_2") (pintype "passive"))
      (node (ref "C17") (pin "2") (pinfunction "2_2") (pintype "passive"))
      (node (ref "C18") (pin "2") (pinfunction "2_2") (pintype "passive"))
      (node (ref "C19") (pin "2") (pinfunction "2_2") (pintype "passive"))
      (node (ref "C2") (pin "2") (pinfunction "2_2") (pintype "passive"))
      (node (ref "C20") (pin "2") (pinfunction "2_2") (pintype "passive"))
      (node (ref "C21") (pin "2") (pinfunction "2_2") (pintype "passive"))
      (node (ref "C3") (pin "2") (pinfunction "2_2") (pintype "passive"))
      (node (ref "C34") (pin "2") (pinfunction "2_2") (pintype "passive"))
      (node (ref "C35") (pin "2") (pinfunction "2_2") (pintype "passive"))
      (node (ref "C36") (pin "2") (pinfunction "2_2") (pintype "passive"))
      (node (ref "C37") (pin "2") (pinfunction "2_2") (pintype "passive"))
      (node (ref "C38") (pin "2") (pinfunction "2_2") (pintype "passive"))
      (node (ref "C4") (pin "2") (pinfunction "2_2") (pintype "passive"))
      (node (ref "C5") (pin "2") (pinfunction "2_2") (pintype "passive"))
      (node (ref "C6") (pin "2") (pinfunction "2_2") (pintype "passive"))
      (node (ref "C7") (pin "2") (pinfunction "2_2") (pintype "passive"))
      (node (ref "C8") (pin "2") (pinfunction "2_2") (pintype "passive"))
      (node (ref "C9") (pin "2") (pinfunction "2_2") (pintype "passive"))
      (node (ref "IC1") (pin "18") (pinfunction "GND1_18") (pintype "bidirectional"))
      (node (ref "IC1") (pin "25") (pinfunction "GND2_25") (pintype "bidirectional"))
      (node (ref "IC1") (pin "34") (pinfunction "GND3_34") (pintype "bidirectional"))
      (node (ref "IC1") (pin "45") (pinfunction "AGND_45") (pintype "bidirectional"))
      (node (ref "IC1") (pin "47") (pinfunction "TEST_47") (pintype "bidirectional"))
      (node (ref "IC1") (pin "9") (pinfunction "GND0_9") (pintype "bidirectional"))
      (node (ref "IC2") (pin "10") (pinfunction "VSS_10") (pintype "power_in"))
      (node (ref "IC2") (pin "20") (pinfunction "VSSA_20") (pintype "power_in"))
      (node (ref "IC2") (pin "27") (pinfunction "VSS_27") (pintype "power_in"))
      (node (ref "IC2") (pin "74") (pinfunction "VSS_74") (pintype "power_in"))
      (node (ref "IC3") (pin "1") (pinfunction "GND_1") (pintype "power_in"))
      (node (ref "IC4") (pin "3") (pinfunction "GND1_3") (pintype "bidirectional"))
      (node (ref "IC4") (pin "5") (pinfunction "GND2_5") (pintype "bidirectional"))
      (node (ref "IC4") (pin "6") (pinfunction "GND3_6") (pintype "bidirectional"))
      (node (ref "IC4") (pin "7") (pinfunction "GND4_7") (pintype "bidirectional"))
      (node (ref "IC6") (pin "16") (pinfunction "GND_16") (pintype "power_in"))
      (node (ref "IC6") (pin "19") (pinfunction "GND_19") (pintype "power_in"))
      (node (ref "IC6") (pin "21") (pinfunction "AGND_21") (pintype "power_in"))
      (node (ref "J1") (pin "1") (pinfunction "1_1") (pintype "passive"))
      (node (ref "J2") (pin "3") (pinfunction "3_3") (pintype "passive"))
      (node (ref "J3") (pin "1") (pinfunction "S_1") (pintype "passive"))
      (node (ref "LED1") (pin "C") (pinfunction "C_C") (pintype "passive"))
      (node (ref "LED2") (pin "C") (pinfunction "C_C") (pintype "passive"))
      (node (ref "LED3") (pin "C") (pinfunction "C_C") (pintype "passive"))
      (node (ref "LED4") (pin "C") (pinfunction "C_C") (pintype "passive"))
      (node (ref "R16") (pin "1") (pinfunction "1_1") (pintype "passive"))
      (node (ref "R3") (pin "1") (pinfunction "1_1") (pintype "passive"))
      (node (ref "R4") (pin "1") (pinfunction "1_1") (pintype "passive"))
      (node (ref "S1") (pin "1") (pinfunction "P_1") (pintype "passive"))
      (node (ref "S1") (pin "2") (pinfunction "P1_2") (pintype "passive"))
      (node (ref "SD1") (pin "10") (pinfunction "CD2/GND_10") (pintype "bidirectional"))
      (node (ref "SD1") (pin "11") (pinfunction "GND_11") (pintype "power_in"))
      (node (ref "SD1") (pin "12") (pinfunction "GND_12") (pintype "power_in"))
      (node (ref "SD1") (pin "13") (pinfunction "GND_13") (pintype "power_in"))
      (node (ref "SD1") (pin "6") (pinfunction "GND_6") (pintype "power_in"))
      (node (ref "SV1") (pin "29") (pinfunction "29_29") (pintype "passive"))
      (node (ref "SV1") (pin "30") (pinfunction "30_30") (pintype "passive"))
      (node (ref "SV10") (pin "1") (pinfunction "1_1") (pintype "passive"))
      (node (ref "SV11") (pin "1") (pinfunction "1_1") (pintype "passive"))
      (node (ref "SV12") (pin "1") (pinfunction "1_1") (pintype "passive"))
      (node (ref "SV13") (pin "1") (pinfunction "1_1") (pintype "passive"))
      (node (ref "SV14") (pin "1") (pinfunction "1_1") (pintype "passive"))
      (node (ref "SV15") (pin "1") (pinfunction "1_1") (pintype "passive"))
      (node (ref "SV16") (pin "1") (pinfunction "1_1") (pintype "passive"))
      (node (ref "SV2") (pin "1") (pinfunction "1_1") (pintype "passive"))
      (node (ref "SV2") (pin "2") (pinfunction "2_2") (pintype "passive"))
      (node (ref "SV3") (pin "1") (pinfunction "1_1") (pintype "passive"))
      (node (ref "SV4") (pin "1") (pinfunction "1_1") (pintype "passive"))
      (node (ref "SV5") (pin "1") (pinfunction "1_1") (pintype "passive"))
      (node (ref "SV6") (pin "1") (pinfunction "1_1") (pintype "passive"))
      (node (ref "SV7") (pin "1") (pinfunction "1_1") (pintype "passive"))
      (node (ref "SV8") (pin "1") (pinfunction "1_1") (pintype "passive"))
      (node (ref "SV9") (pin "1") (pinfunction "1_1") (pintype "passive"))
      (node (ref "USB1") (pin "GND") (pinfunction "GND_GND") (pintype "power_in"))
      (node (ref "USB1") (pin "GND@1") (pinfunction "GND_GND@1") (pintype "power_in"))
      (node (ref "USB1") (pin "GND@2") (pinfunction "GND_GND@2") (pintype "power_in"))
      (node (ref "USB1") (pin "GND@3") (pinfunction "GND_GND@3") (pintype "power_in"))
      (node (ref "USB1") (pin "GND@4") (pinfunction "GND_GND@4") (pintype "power_in"))
      (node (ref "USB1") (pin "ID") (pinfunction "ID_ID") (pintype "bidirectional"))
    )
    (net (code "95") (name "Net-(IC1-3V3OUT)") (class "Default")
      (node (ref "C11") (pin "1") (pinfunction "1_1") (pintype "passive"))
      (node (ref "IC1") (pin "6") (pinfunction "3V3OUT_6") (pintype "bidirectional"))
    )
    (net (code "96") (name "Net-(IC1-AVVC)") (class "Default")
      (node (ref "C10") (pin "1") (pinfunction "1_1") (pintype "passive"))
      (node (ref "IC1") (pin "46") (pinfunction "AVVC_46") (pintype "bidirectional"))
      (node (ref "R1") (pin "1") (pinfunction "1_1") (pintype "passive"))
    )
    (net (code "97") (name "Net-(IC1-RSTOUT#)") (class "Default")
      (node (ref "IC1") (pin "5") (pinfunction "RSTOUT#_5") (pintype "bidirectional"))
      (node (ref "R10") (pin "1") (pinfunction "1_1") (pintype "passive"))
    )
    (net (code "98") (name "Net-(IC1-USBDM)") (class "Default")
      (node (ref "IC1") (pin "8") (pinfunction "USBDM_8") (pintype "bidirectional"))
      (node (ref "USB1") (pin "D-") (pinfunction "D-_D-") (pintype "bidirectional"))
    )
    (net (code "99") (name "Net-(IC1-USBDP)") (class "Default")
      (node (ref "IC1") (pin "7") (pinfunction "USBDP_7") (pintype "bidirectional"))
      (node (ref "R10") (pin "2") (pinfunction "2_2") (pintype "passive"))
      (node (ref "USB1") (pin "D+") (pinfunction "D+_D+") (pintype "bidirectional"))
    )
    (net (code "100") (name "Net-(IC1-XTIN)") (class "Default")
      (node (ref "C13") (pin "2") (pinfunction "2_2") (pintype "passive"))
      (node (ref "IC1") (pin "43") (pinfunction "XTIN_43") (pintype "bidirectional"))
      (node (ref "Q3") (pin "2") (pinfunction "2_2") (pintype "passive"))
    )
    (net (code "101") (name "Net-(IC1-XTOUT)") (class "Default")
      (node (ref "C12") (pin "2") (pinfunction "2_2") (pintype "passive"))
      (node (ref "IC1") (pin "44") (pinfunction "XTOUT_44") (pintype "bidirectional"))
      (node (ref "Q3") (pin "1") (pinfunction "1_1") (pintype "passive"))
    )
    (net (code "102") (name "Net-(IC2-PDR_ON)") (class "Default")
      (node (ref "IC2") (pin "99") (pinfunction "PDR_ON_99") (pintype "bidirectional"))
      (node (ref "J1") (pin "2") (pinfunction "2_2") (pintype "passive"))
    )
    (net (code "103") (name "Net-(IC2-VCAP_1)") (class "Default")
      (node (ref "C4") (pin "1") (pinfunction "1_1") (pintype "passive"))
      (node (ref "IC2") (pin "49") (pinfunction "VCAP_1_49") (pintype "bidirectional"))
    )
    (net (code "104") (name "Net-(IC2-VCAP_2)") (class "Default")
      (node (ref "C3") (pin "1") (pinfunction "1_1") (pintype "passive"))
      (node (ref "IC2") (pin "73") (pinfunction "VCAP_2_73") (pintype "bidirectional"))
    )
    (net (code "105") (name "Net-(IC2-VDD-Pad19)") (class "Default")
      (node (ref "IC2") (pin "19") (pinfunction "VDD_19") (pintype "power_in"))
      (node (ref "J2") (pin "2") (pinfunction "2_2") (pintype "passive"))
    )
    (net (code "106") (name "Net-(IC6A-DCOUPL)") (class "Default")
      (node (ref "C16") (pin "1") (pinfunction "1_1") (pintype "passive"))
      (node (ref "IC6") (pin "5") (pinfunction "DCOUPL_5") (pintype "power_in"))
    )
    (net (code "107") (name "Net-(IC6A-RBIAS)") (class "Default")
      (node (ref "IC6") (pin "17") (pinfunction "RBIAS_17") (pintype "bidirectional"))
      (node (ref "R16") (pin "2") (pinfunction "2_2") (pintype "passive"))
    )
    (net (code "108") (name "Net-(IC6A-RF-N)") (class "Default")
      (node (ref "C121") (pin "2") (pinfunction "2_2") (pintype "passive"))
      (node (ref "C131") (pin "1") (pinfunction "1_1") (pintype "passive"))
      (node (ref "IC6") (pin "12") (pinfunction "RF-P_12") (pintype "bidirectional"))
      (node (ref "IC6") (pin "13") (pinfunction "RF-N_13") (pintype "bidirectional"))
    )
    (net (code "109") (name "Net-(IC6A-XOSC-1)") (class "Default")
      (node (ref "C14") (pin "2") (pinfunction "2_2") (pintype "passive"))
      (node (ref "IC6") (pin "8") (pinfunction "XOSC-1_8") (pintype "input"))
      (node (ref "Q4") (pin "2") (pinfunction "2_2") (pintype "passive"))
    )
    (net (code "110") (name "Net-(IC6A-XOSC-2)") (class "Default")
      (node (ref "C15") (pin "2") (pinfunction "2_2") (pintype "passive"))
      (node (ref "IC6") (pin "10") (pinfunction "XOSC-2_10") (pintype "output"))
      (node (ref "Q4") (pin "1") (pinfunction "1_1") (pintype "passive"))
    )
    (net (code "111") (name "Net-(J3B-S)") (class "Default")
      (node (ref "J3") (pin "2") (pinfunction "S_2") (pintype "passive"))
      (node (ref "POWER") (pin "2") (pinfunction "2_2") (pintype "passive"))
    )
    (net (code "112") (name "Net-(L1-Pad2)") (class "Default")
      (node (ref "L1") (pin "2") (pinfunction "2_2") (pintype "passive"))
      (node (ref "USB1") (pin "VBUS") (pinfunction "VBUS_VBUS") (pintype "power_in"))
    )
    (net (code "113") (name "Net-(LED1-PadA)") (class "Default")
      (node (ref "LED1") (pin "A") (pinfunction "A_A") (pintype "passive"))
      (node (ref "R6") (pin "1") (pinfunction "1_1") (pintype "passive"))
    )
    (net (code "114") (name "Net-(LED2-PadA)") (class "Default")
      (node (ref "LED2") (pin "A") (pinfunction "A_A") (pintype "passive"))
      (node (ref "R7") (pin "1") (pinfunction "1_1") (pintype "passive"))
    )
    (net (code "115") (name "Net-(LED3-PadA)") (class "Default")
      (node (ref "LED3") (pin "A") (pinfunction "A_A") (pintype "passive"))
      (node (ref "R8") (pin "1") (pinfunction "1_1") (pintype "passive"))
    )
    (net (code "116") (name "Net-(LED4-PadA)") (class "Default")
      (node (ref "LED4") (pin "A") (pinfunction "A_A") (pintype "passive"))
      (node (ref "R9") (pin "1") (pinfunction "1_1") (pintype "passive"))
    )
    (net (code "117") (name "unconnected-(IC1-ACBUS0-Pad15)") (class "Default")
      (node (ref "IC1") (pin "15") (pinfunction "ACBUS0_15") (pintype "bidirectional"))
    )
    (net (code "118") (name "unconnected-(IC1-ACBUS1-Pad13)") (class "Default")
      (node (ref "IC1") (pin "13") (pinfunction "ACBUS1_13") (pintype "bidirectional"))
    )
    (net (code "119") (name "unconnected-(IC1-ACBUS2-Pad12)") (class "Default")
      (node (ref "IC1") (pin "12") (pinfunction "ACBUS2_12") (pintype "bidirectional"))
    )
    (net (code "120") (name "unconnected-(IC1-ACBUS3-Pad11)") (class "Default")
      (node (ref "IC1") (pin "11") (pinfunction "ACBUS3_11") (pintype "bidirectional"))
    )
    (net (code "121") (name "unconnected-(IC1-ADBUS5-Pad19)") (class "Default")
      (node (ref "IC1") (pin "19") (pinfunction "ADBUS5_19") (pintype "bidirectional"))
    )
    (net (code "122") (name "unconnected-(IC1-ADBUS7-Pad16)") (class "Default")
      (node (ref "IC1") (pin "16") (pinfunction "ADBUS7_16") (pintype "bidirectional"))
    )
    (net (code "123") (name "unconnected-(IC1-BCBUS0-Pad30)") (class "Default")
      (node (ref "IC1") (pin "30") (pinfunction "BCBUS0_30") (pintype "bidirectional"))
    )
    (net (code "124") (name "unconnected-(IC1-BCBUS1-Pad29)") (class "Default")
      (node (ref "IC1") (pin "29") (pinfunction "BCBUS1_29") (pintype "bidirectional"))
    )
    (net (code "125") (name "unconnected-(IC1-BCBUS2-Pad28)") (class "Default")
      (node (ref "IC1") (pin "28") (pinfunction "BCBUS2_28") (pintype "bidirectional"))
    )
    (net (code "126") (name "unconnected-(IC1-BCBUS3-Pad27)") (class "Default")
      (node (ref "IC1") (pin "27") (pinfunction "BCBUS3_27") (pintype "bidirectional"))
    )
    (net (code "127") (name "unconnected-(IC1-BDBUS2-Pad38)") (class "Default")
      (node (ref "IC1") (pin "38") (pinfunction "BDBUS2_38") (pintype "bidirectional"))
    )
    (net (code "128") (name "unconnected-(IC1-BDBUS3-Pad37)") (class "Default")
      (node (ref "IC1") (pin "37") (pinfunction "BDBUS3_37") (pintype "bidirectional"))
    )
    (net (code "129") (name "unconnected-(IC1-BDBUS4-Pad36)") (class "Default")
      (node (ref "IC1") (pin "36") (pinfunction "BDBUS4_36") (pintype "bidirectional"))
    )
    (net (code "130") (name "unconnected-(IC1-BDBUS5-Pad35)") (class "Default")
      (node (ref "IC1") (pin "35") (pinfunction "BDBUS5_35") (pintype "bidirectional"))
    )
    (net (code "131") (name "unconnected-(IC1-BDBUS6-Pad33)") (class "Default")
      (node (ref "IC1") (pin "33") (pinfunction "BDBUS6_33") (pintype "bidirectional"))
    )
    (net (code "132") (name "unconnected-(IC1-BDBUS7-Pad32)") (class "Default")
      (node (ref "IC1") (pin "32") (pinfunction "BDBUS7_32") (pintype "bidirectional"))
    )
    (net (code "133") (name "unconnected-(IC1-PWREN#-Pad41)") (class "Default")
      (node (ref "IC1") (pin "41") (pinfunction "PWREN#_41") (pintype "bidirectional"))
    )
    (net (code "134") (name "unconnected-(IC4-TEST-Pad2)") (class "Default")
      (node (ref "IC4") (pin "2") (pinfunction "TEST_2") (pintype "bidirectional"))
    )
    (net (code "135") (name "unconnected-(POWER-Pad3)") (class "Default")
      (node (ref "POWER") (pin "3") (pinfunction "3_3") (pintype "passive"))
    )
  )
)
